# Main_SCH.net
KiCad netlist of a schematic drawn in Altium Designer
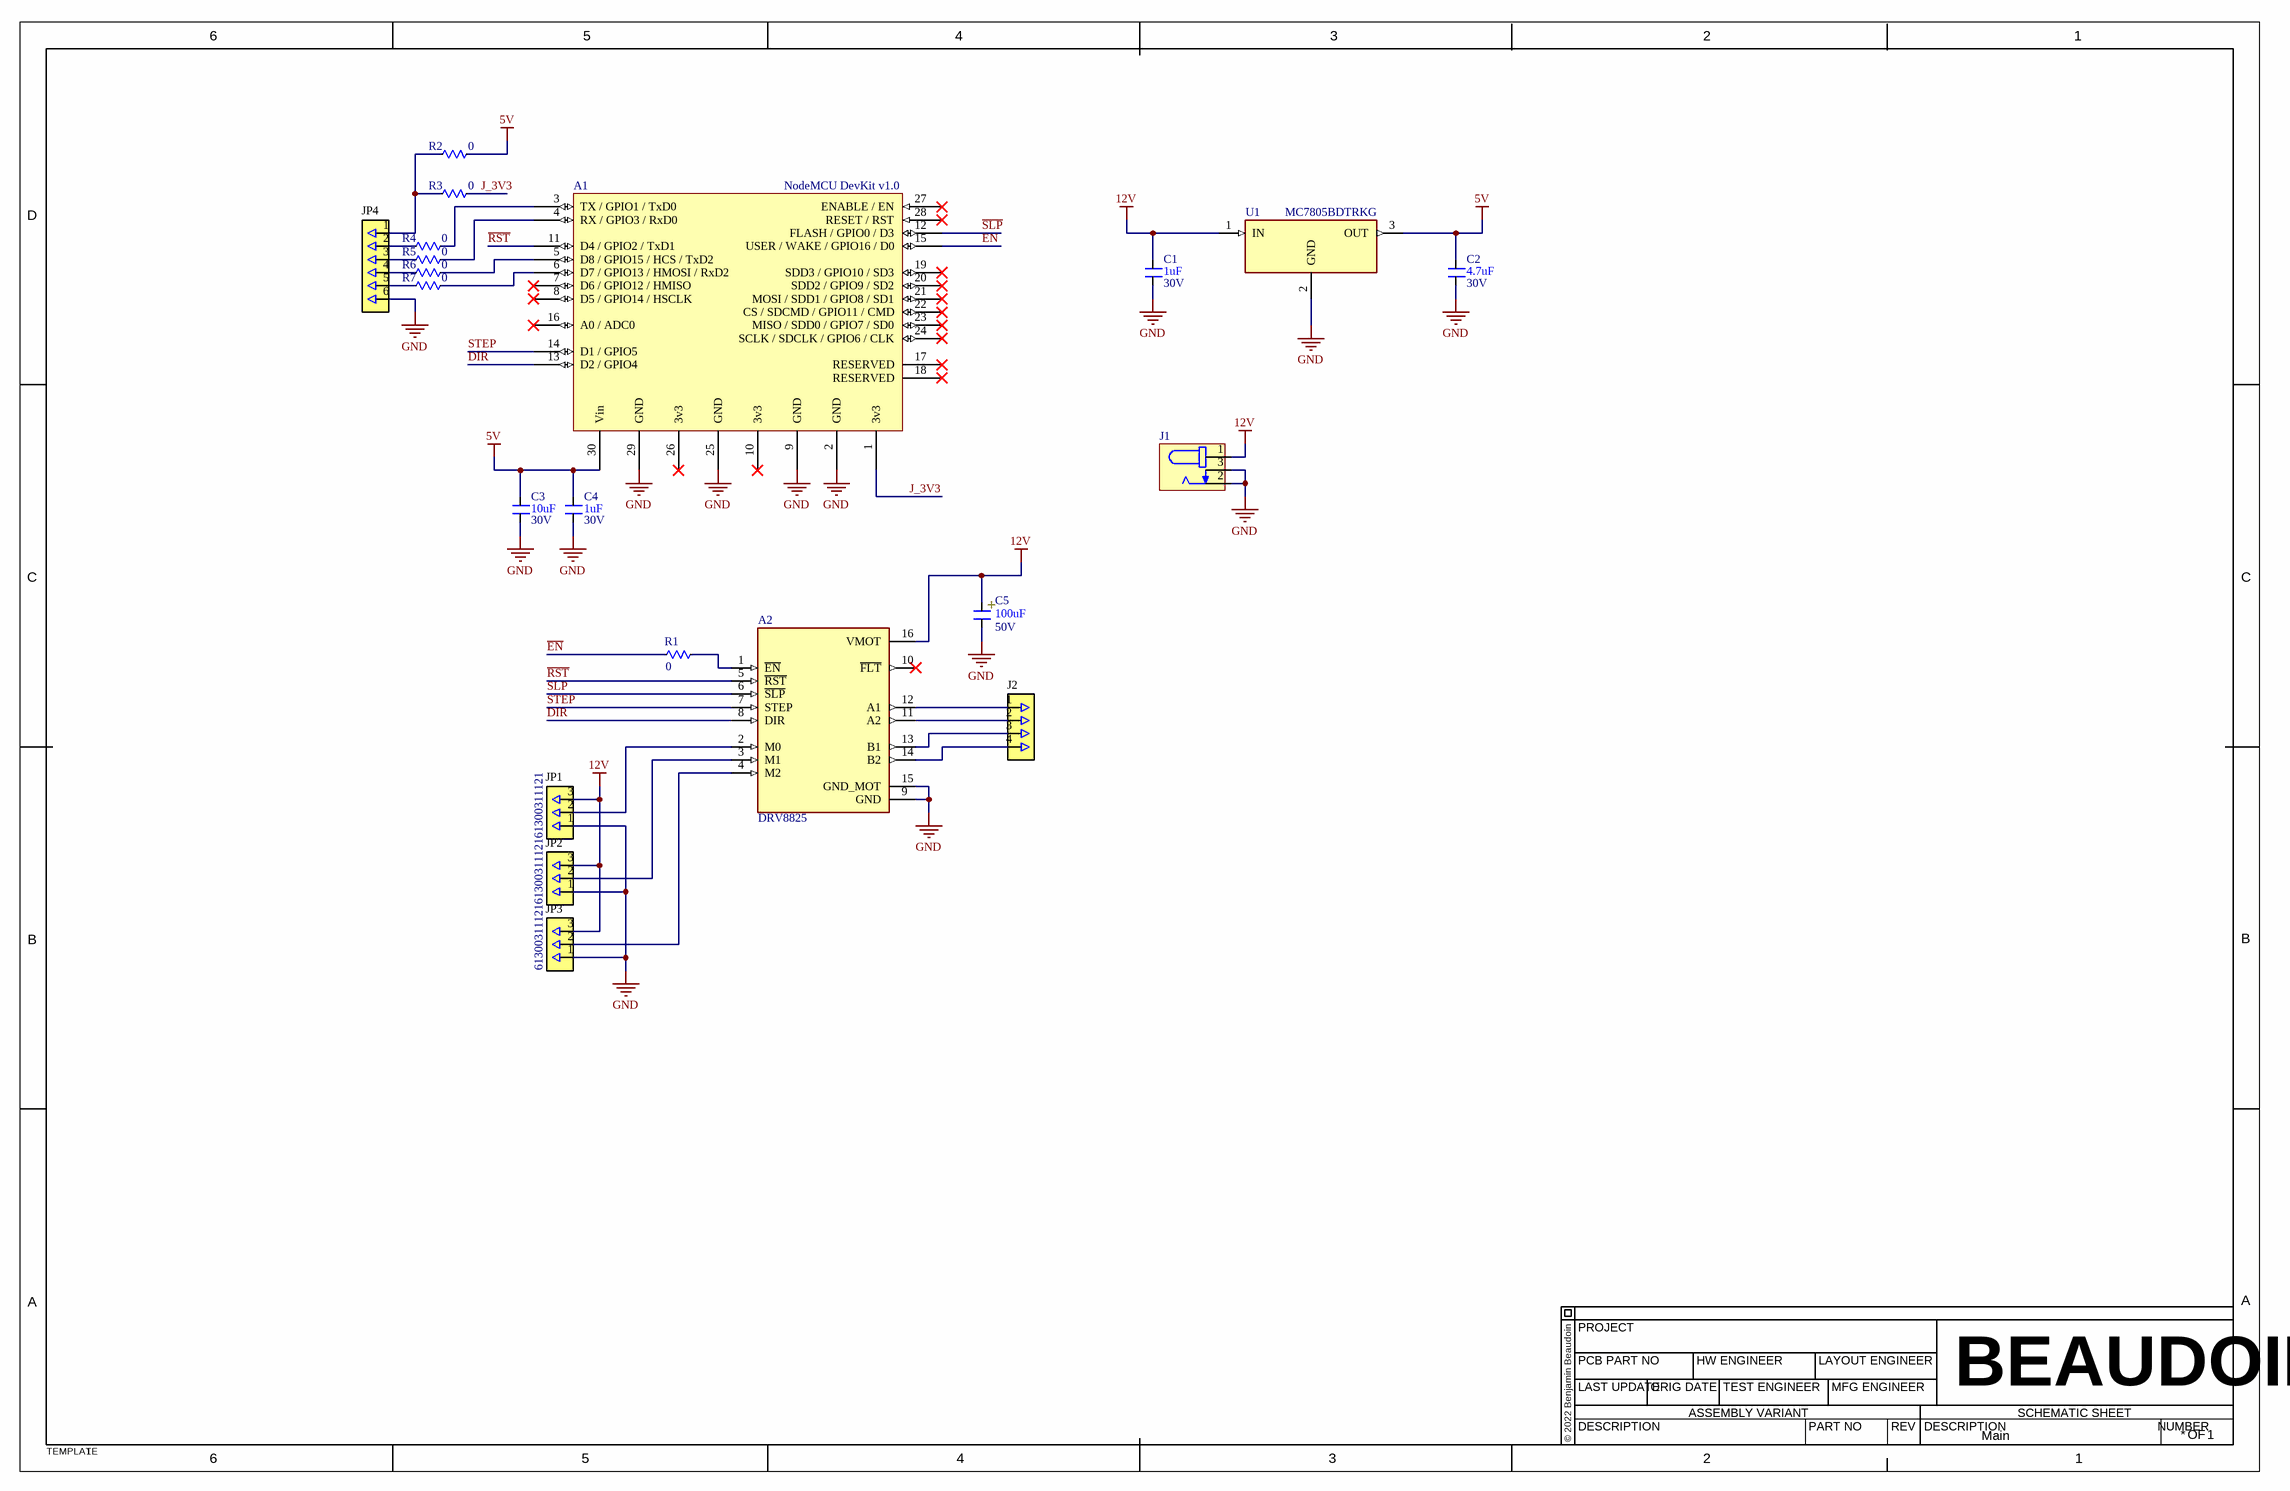
[diagram p0: Main_SCH.SchDoc]

(export (version "E")
  (design (tool "Eeschema 10.0.6"))
  (components
    (comp (ref "A1")
      (value "NodeMCU DevKit v1.0")
      (footprint "NodeMCU DevKit v1.0 - No Labels")
      (libsource (lib "Motorized_Blinds_IntLib") (part "NodeMCU DevKit v1.0"))
    )
    (comp (ref "A2")
      (value "DRV8825")
      (footprint "IC_DRV8825_STEPPER_MOTOR_DRIVER_CARRIER")
      (description "DRV8825 Motor Controller/Driver Power Management Evaluation Board")
      (fields (field (name "MANUFACTURER") "Pololu"))
      (libsource (lib "Motorized_Blinds_IntLib") (part "DRV8825_STEPPER_MOTOR_DRIVER_CARRIER"))
    )
    (comp (ref "C1")
      (value "1uF")
      (footprint "C0603")
      (description "SMCAP NoPol")
      (fields (field (name "VMAX") "30V"))
      (libsource (lib "Motorized_Blinds_IntLib") (part "CAP-NoPol"))
    )
    (comp (ref "C2")
      (value "4.7uF")
      (footprint "C0603")
      (description "SMCAP NoPol")
      (fields (field (name "VMAX") "30V"))
      (libsource (lib "Motorized_Blinds_IntLib") (part "CAP-NoPol"))
    )
    (comp (ref "C3")
      (value "10uF")
      (footprint "C0805")
      (description "SMCAP NoPol")
      (fields (field (name "VMAX") "30V"))
      (libsource (lib "Motorized_Blinds_IntLib") (part "CAP-NoPol"))
    )
    (comp (ref "C4")
      (value "1uF")
      (footprint "C0603")
      (description "SMCAP NoPol")
      (fields (field (name "VMAX") "30V"))
      (libsource (lib "Motorized_Blinds_IntLib") (part "CAP-NoPol"))
    )
    (comp (ref "C5")
      (value "100uF")
      (footprint "CAPAE1050X1050N")
      (description "CAP ALUM 100UF 20% 50V SMD")
      (fields (field (name "MANUFACTURER") "Vishay") (field (name "VMAX") "50V"))
      (libsource (lib "Motorized_Blinds_IntLib") (part "CAP-Pol_MAL214699103E3"))
    )
    (comp (ref "J1")
      (value "PJ-036AH-SMT-TR")
      (footprint "CUI_PJ-036AH-SMT-TR")
      (description "2.0 x 6.3 mm, 5.0 A, Horizontal, Surface Mount _SMT_, Dc Power Jack Connector")
      (fields (field (name "MANUFACTURER") "CUI Devices"))
      (libsource (lib "Motorized_Blinds_IntLib") (part "PJ-036AH-SMT-TR"))
    )
    (comp (ref "J2")
      (value "~")
      (footprint "JP_J4_2.54mm")
      (description "CONN HEADER VERT 4POS 2.54MM")
      (libsource (lib "Motorized_Blinds_IntLib") (part "JP_J4_2.54mm"))
    )
    (comp (ref "JP1")
      (value "61300311121")
      (footprint "JP_61300311121")
      (description "CONN HEADER VERT 3POS 2.54MM")
      (libsource (lib "Motorized_Blinds_IntLib") (part "JP_61300311121"))
    )
    (comp (ref "JP2")
      (value "61300311121")
      (footprint "JP_61300311121")
      (description "CONN HEADER VERT 3POS 2.54MM")
      (libsource (lib "Motorized_Blinds_IntLib") (part "JP_61300311121"))
    )
    (comp (ref "JP3")
      (value "61300311121")
      (footprint "JP_61300311121")
      (description "CONN HEADER VERT 3POS 2.54MM")
      (libsource (lib "Motorized_Blinds_IntLib") (part "JP_61300311121"))
    )
    (comp (ref "JP4")
      (value "~")
      (footprint "JP_J6_2.54mm")
      (description "CONN HEADER VERT 6POS 2.54MM")
      (libsource (lib "Motorized_Blinds_IntLib") (part "JP_J6_2.54mm"))
    )
    (comp (ref "R1")
      (value "0")
      (footprint "R0603")
      (description "SMRES")
      (libsource (lib "Motorized_Blinds_IntLib") (part "Res"))
    )
    (comp (ref "R2")
      (value "0")
      (footprint "R0603")
      (description "SMRES")
      (libsource (lib "Motorized_Blinds_IntLib") (part "Res"))
    )
    (comp (ref "R3")
      (value "0")
      (footprint "R0603")
      (description "SMRES")
      (libsource (lib "Motorized_Blinds_IntLib") (part "Res"))
    )
    (comp (ref "R4")
      (value "0")
      (footprint "R0603")
      (description "SMRES")
      (libsource (lib "Motorized_Blinds_IntLib") (part "Res"))
    )
    (comp (ref "R5")
      (value "0")
      (footprint "R0603")
      (description "SMRES")
      (libsource (lib "Motorized_Blinds_IntLib") (part "Res"))
    )
    (comp (ref "R6")
      (value "0")
      (footprint "R0603")
      (description "SMRES")
      (libsource (lib "Motorized_Blinds_IntLib") (part "Res"))
    )
    (comp (ref "R7")
      (value "0")
      (footprint "R0603")
      (description "SMRES")
      (libsource (lib "Motorized_Blinds_IntLib") (part "Res"))
    )
    (comp (ref "U1")
      (value "MC7805BDTRKG")
      (footprint "DPAK229P990X238-4N")
      (description "Linear Voltage Regulator IC 1 Output 1A DPAK")
      (fields (field (name "MANUFACTURER") "ON Semiconductor"))
      (libsource (lib "Motorized_Blinds_IntLib") (part "MC7805BDTRKG"))
    )
  )
  (nets
    (net (code "1") (name "/DIR") (class "Default")
      (node (ref "A1") (pin "13") (pinfunction "D2_/_GPIO4_13") (pintype "bidirectional"))
      (node (ref "A2") (pin "8") (pinfunction "DIR_8") (pintype "input"))
    )
    (net (code "2") (name "/J_3V3") (class "Default")
      (node (ref "A1") (pin "1") (pinfunction "3v3_1") (pintype "power_in"))
      (node (ref "R3") (pin "2") (pintype "passive"))
    )
    (net (code "3") (name "/STEP") (class "Default")
      (node (ref "A1") (pin "14") (pinfunction "D1_/_GPIO5_14") (pintype "bidirectional"))
      (node (ref "A2") (pin "7") (pinfunction "STEP_7") (pintype "input"))
    )
    (net (code "4") (name "/~{EN}") (class "Default")
      (node (ref "A1") (pin "15") (pinfunction "USER_/_WAKE_/_GPIO16_/_D0_15") (pintype "bidirectional"))
      (node (ref "R1") (pin "1") (pintype "passive"))
    )
    (net (code "5") (name "/~{RST}") (class "Default")
      (node (ref "A1") (pin "11") (pinfunction "D4_/_GPIO2_/_TxD1_11") (pintype "bidirectional"))
      (node (ref "A2") (pin "5") (pinfunction "~{RST}_5") (pintype "input"))
    )
    (net (code "6") (name "/~{SLP}") (class "Default")
      (node (ref "A1") (pin "12") (pinfunction "FLASH_/_GPIO0_/_D3_12") (pintype "bidirectional"))
      (node (ref "A2") (pin "6") (pinfunction "~{SLP}_6") (pintype "input"))
    )
    (net (code "7") (name "5V") (class "Default")
      (node (ref "A1") (pin "30") (pinfunction "Vin_30") (pintype "passive"))
      (node (ref "C2") (pin "1") (pintype "passive"))
      (node (ref "C3") (pin "1") (pintype "passive"))
      (node (ref "C4") (pin "1") (pintype "passive"))
      (node (ref "R2") (pin "2") (pintype "passive"))
      (node (ref "U1") (pin "3") (pinfunction "OUT_3") (pintype "output"))
    )
    (net (code "8") (name "12V") (class "Default")
      (node (ref "A2") (pin "16") (pinfunction "VMOT_16") (pintype "power_in"))
      (node (ref "C1") (pin "1") (pintype "passive"))
      (node (ref "C5") (pin "1") (pintype "passive"))
      (node (ref "J1") (pin "1") (pinfunction "1_1") (pintype "passive"))
      (node (ref "JP1") (pin "3") (pintype "passive"))
      (node (ref "JP2") (pin "3") (pintype "passive"))
      (node (ref "JP3") (pin "3") (pintype "passive"))
      (node (ref "U1") (pin "1") (pinfunction "IN_1") (pintype "input"))
    )
    (net (code "9") (name "GND") (class "Default")
      (node (ref "A1") (pin "2") (pinfunction "GND_2") (pintype "power_in"))
      (node (ref "A1") (pin "25") (pinfunction "GND_25") (pintype "power_in"))
      (node (ref "A1") (pin "29") (pinfunction "GND_29") (pintype "passive"))
      (node (ref "A1") (pin "9") (pinfunction "GND_9") (pintype "power_in"))
      (node (ref "A2") (pin "15") (pinfunction "GND_MOT_15") (pintype "power_in"))
      (node (ref "A2") (pin "9") (pinfunction "GND_9") (pintype "power_in"))
      (node (ref "C1") (pin "2") (pintype "passive"))
      (node (ref "C2") (pin "2") (pintype "passive"))
      (node (ref "C3") (pin "2") (pintype "passive"))
      (node (ref "C4") (pin "2") (pintype "passive"))
      (node (ref "C5") (pin "2") (pintype "passive"))
      (node (ref "J1") (pin "2") (pinfunction "2_2") (pintype "passive"))
      (node (ref "J1") (pin "3") (pinfunction "3_3") (pintype "passive"))
      (node (ref "JP1") (pin "1") (pintype "passive"))
      (node (ref "JP2") (pin "1") (pintype "passive"))
      (node (ref "JP3") (pin "1") (pintype "passive"))
      (node (ref "JP4") (pin "6") (pintype "passive"))
      (node (ref "U1") (pin "2") (pinfunction "GND_2") (pintype "power_in"))
    )
    (net (code "10") (name "Net-(A1-D7_{slash}_GPIO13_{slash}_HMOSI_{slash}_RxD2)") (class "Default")
      (node (ref "A1") (pin "6") (pinfunction "D7_/_GPIO13_/_HMOSI_/_RxD2_6") (pintype "bidirectional"))
      (node (ref "R7") (pin "2") (pintype "passive"))
    )
    (net (code "11") (name "Net-(A1-D8_{slash}_GPIO15_{slash}_HCS_{slash}_TxD2)") (class "Default")
      (node (ref "A1") (pin "5") (pinfunction "D8_/_GPIO15_/_HCS_/_TxD2_5") (pintype "bidirectional"))
      (node (ref "R6") (pin "2") (pintype "passive"))
    )
    (net (code "12") (name "Net-(A1-RX_{slash}_GPIO3_{slash}_RxD0)") (class "Default")
      (node (ref "A1") (pin "4") (pinfunction "RX_/_GPIO3_/_RxD0_4") (pintype "bidirectional"))
      (node (ref "R5") (pin "2") (pintype "passive"))
    )
    (net (code "13") (name "Net-(A1-TX_{slash}_GPIO1_{slash}_TxD0)") (class "Default")
      (node (ref "A1") (pin "3") (pinfunction "TX_/_GPIO1_/_TxD0_3") (pintype "bidirectional"))
      (node (ref "R4") (pin "2") (pintype "passive"))
    )
    (net (code "14") (name "Net-(A2-A1)") (class "Default")
      (node (ref "A2") (pin "12") (pinfunction "A1_12") (pintype "output"))
      (node (ref "J2") (pin "1") (pintype "passive"))
    )
    (net (code "15") (name "Net-(A2-A2)") (class "Default")
      (node (ref "A2") (pin "11") (pinfunction "A2_11") (pintype "output"))
      (node (ref "J2") (pin "2") (pintype "passive"))
    )
    (net (code "16") (name "Net-(A2-B1)") (class "Default")
      (node (ref "A2") (pin "13") (pinfunction "B1_13") (pintype "output"))
      (node (ref "J2") (pin "3") (pintype "passive"))
    )
    (net (code "17") (name "Net-(A2-B2)") (class "Default")
      (node (ref "A2") (pin "14") (pinfunction "B2_14") (pintype "output"))
      (node (ref "J2") (pin "4") (pintype "passive"))
    )
    (net (code "18") (name "Net-(A2-M0)") (class "Default")
      (node (ref "A2") (pin "2") (pinfunction "M0_2") (pintype "input"))
      (node (ref "JP1") (pin "2") (pintype "passive"))
    )
    (net (code "19") (name "Net-(A2-M1)") (class "Default")
      (node (ref "A2") (pin "3") (pinfunction "M1_3") (pintype "input"))
      (node (ref "JP2") (pin "2") (pintype "passive"))
    )
    (net (code "20") (name "Net-(A2-M2)") (class "Default")
      (node (ref "A2") (pin "4") (pinfunction "M2_4") (pintype "input"))
      (node (ref "JP3") (pin "2") (pintype "passive"))
    )
    (net (code "21") (name "Net-(A2-~{EN})") (class "Default")
      (node (ref "A2") (pin "1") (pinfunction "~{EN}_1") (pintype "input"))
      (node (ref "R1") (pin "2") (pintype "passive"))
    )
    (net (code "22") (name "Net-(JP4-Pad1)") (class "Default")
      (node (ref "JP4") (pin "1") (pintype "passive"))
      (node (ref "R2") (pin "1") (pintype "passive"))
      (node (ref "R3") (pin "1") (pintype "passive"))
    )
    (net (code "23") (name "Net-(JP4-Pad2)") (class "Default")
      (node (ref "JP4") (pin "2") (pintype "passive"))
      (node (ref "R4") (pin "1") (pintype "passive"))
    )
    (net (code "24") (name "Net-(JP4-Pad3)") (class "Default")
      (node (ref "JP4") (pin "3") (pintype "passive"))
      (node (ref "R5") (pin "1") (pintype "passive"))
    )
    (net (code "25") (name "Net-(JP4-Pad4)") (class "Default")
      (node (ref "JP4") (pin "4") (pintype "passive"))
      (node (ref "R6") (pin "1") (pintype "passive"))
    )
    (net (code "26") (name "Net-(JP4-Pad5)") (class "Default")
      (node (ref "JP4") (pin "5") (pintype "passive"))
      (node (ref "R7") (pin "1") (pintype "passive"))
    )
    (net (code "27") (name "unconnected-(A1-3v3-Pad10)") (class "Default")
      (node (ref "A1") (pin "10") (pinfunction "3v3_10") (pintype "power_in+no_connect"))
    )
    (net (code "28") (name "unconnected-(A1-3v3-Pad26)") (class "Default")
      (node (ref "A1") (pin "26") (pinfunction "3v3_26") (pintype "power_in+no_connect"))
    )
    (net (code "29") (name "unconnected-(A1-A0_{slash}_ADC0-Pad16)") (class "Default")
      (node (ref "A1") (pin "16") (pinfunction "A0_/_ADC0_16") (pintype "bidirectional+no_connect"))
    )
    (net (code "30") (name "unconnected-(A1-CS_{slash}_SDCMD_{slash}_GPIO11_{slash}_CMD-Pad22)") (class "Default")
      (node (ref "A1") (pin "22") (pinfunction "CS_/_SDCMD_/_GPIO11_/_CMD_22") (pintype "bidirectional+no_connect"))
    )
    (net (code "31") (name "unconnected-(A1-D5_{slash}_GPIO14_{slash}_HSCLK-Pad8)") (class "Default")
      (node (ref "A1") (pin "8") (pinfunction "D5_/_GPIO14_/_HSCLK_8") (pintype "bidirectional+no_connect"))
    )
    (net (code "32") (name "unconnected-(A1-D6_{slash}_GPIO12_{slash}_HMISO-Pad7)") (class "Default")
      (node (ref "A1") (pin "7") (pinfunction "D6_/_GPIO12_/_HMISO_7") (pintype "bidirectional+no_connect"))
    )
    (net (code "33") (name "unconnected-(A1-ENABLE_{slash}_EN-Pad27)") (class "Default")
      (node (ref "A1") (pin "27") (pinfunction "ENABLE_/_EN_27") (pintype "input+no_connect"))
    )
    (net (code "34") (name "unconnected-(A1-MISO_{slash}_SDD0_{slash}_GPIO7_{slash}_SD0-Pad23)") (class "Default")
      (node (ref "A1") (pin "23") (pinfunction "MISO_/_SDD0_/_GPIO7_/_SD0_23") (pintype "bidirectional+no_connect"))
    )
    (net (code "35") (name "unconnected-(A1-MOSI_{slash}_SDD1_{slash}_GPIO8_{slash}_SD1-Pad21)") (class "Default")
      (node (ref "A1") (pin "21") (pinfunction "MOSI_/_SDD1_/_GPIO8_/_SD1_21") (pintype "bidirectional+no_connect"))
    )
    (net (code "36") (name "unconnected-(A1-RESERVED-Pad17)") (class "Default")
      (node (ref "A1") (pin "17") (pinfunction "RESERVED_17") (pintype "passive+no_connect"))
    )
    (net (code "37") (name "unconnected-(A1-RESERVED-Pad18)") (class "Default")
      (node (ref "A1") (pin "18") (pinfunction "RESERVED_18") (pintype "passive+no_connect"))
    )
    (net (code "38") (name "unconnected-(A1-RESET_{slash}_RST-Pad28)") (class "Default")
      (node (ref "A1") (pin "28") (pinfunction "RESET_/_RST_28") (pintype "input+no_connect"))
    )
    (net (code "39") (name "unconnected-(A1-SCLK_{slash}_SDCLK_{slash}_GPIO6_{slash}_CLK-Pad24)") (class "Default")
      (node (ref "A1") (pin "24") (pinfunction "SCLK_/_SDCLK_/_GPIO6_/_CLK_24") (pintype "bidirectional+no_connect"))
    )
    (net (code "40") (name "unconnected-(A1-SDD2_{slash}_GPIO9_{slash}_SD2-Pad20)") (class "Default")
      (node (ref "A1") (pin "20") (pinfunction "SDD2_/_GPIO9_/_SD2_20") (pintype "bidirectional+no_connect"))
    )
    (net (code "41") (name "unconnected-(A1-SDD3_{slash}_GPIO10_{slash}_SD3-Pad19)") (class "Default")
      (node (ref "A1") (pin "19") (pinfunction "SDD3_/_GPIO10_/_SD3_19") (pintype "bidirectional+no_connect"))
    )
    (net (code "42") (name "unconnected-(A2-~{FLT}-Pad10)") (class "Default")
      (node (ref "A2") (pin "10") (pinfunction "~{FLT}_10") (pintype "output+no_connect"))
    )
  )
)
